# circuit.net
KiCad netlist of a schematic drawn in EAGLE
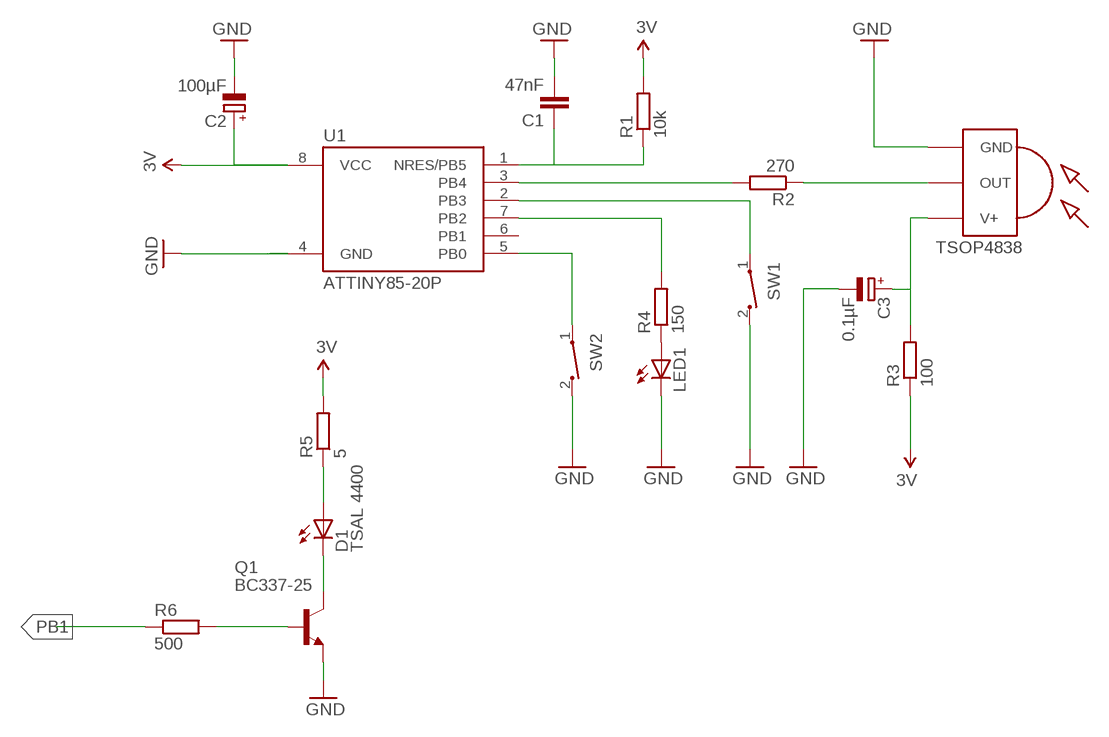
[diagram p0: schematic, sheet 1]

(export (version "E")
  (design (tool "Eeschema 10.0.6"))
  (components
    (comp (ref "C1")
      (value "47nF")
      (footprint "eagle-import:C025-025X050")
      (libsource (lib "eagle-import") (part "C-EU025-025X050"))
    )
    (comp (ref "C2")
      (value "100µF")
      (footprint "eagle-import:085CS_1AR")
      (libsource (lib "eagle-import") (part "CPOL-EU085CS-1AR"))
    )
    (comp (ref "C3")
      (value "0.1µF")
      (footprint "eagle-import:085CS_1AR")
      (libsource (lib "eagle-import") (part "CPOL-EU085CS-1AR"))
    )
    (comp (ref "D1")
      (value "TSAL 4400")
      (footprint "eagle-import:SFH482")
      (libsource (lib "eagle-import") (part "SFH482"))
    )
    (comp (ref "LED1")
      (value "LED5MM")
      (footprint "eagle-import:LED5MM")
      (libsource (lib "eagle-import") (part "LED5MM"))
    )
    (comp (ref "Q1")
      (value "BC337-25")
      (footprint "eagle-import:TO92")
      (libsource (lib "eagle-import") (part "BC337"))
    )
    (comp (ref "R1")
      (value "10k")
      (footprint "eagle-import:0204V")
      (libsource (lib "eagle-import") (part "R-EU_0204/2V"))
    )
    (comp (ref "R2")
      (value "270")
      (footprint "eagle-import:0204V")
      (libsource (lib "eagle-import") (part "R-EU_0204/2V"))
    )
    (comp (ref "R3")
      (value "100")
      (footprint "eagle-import:0204V")
      (libsource (lib "eagle-import") (part "R-EU_0204/2V"))
    )
    (comp (ref "R4")
      (value "150")
      (footprint "eagle-import:0204V")
      (libsource (lib "eagle-import") (part "R-EU_0204/2V"))
    )
    (comp (ref "R5")
      (value "5")
      (footprint "eagle-import:0204V")
      (libsource (lib "eagle-import") (part "R-EU_0204/2V"))
    )
    (comp (ref "R6")
      (value "500")
      (footprint "eagle-import:0204V")
      (libsource (lib "eagle-import") (part "R-EU_0204/2V"))
    )
    (comp (ref "SW1")
      (value "CT10-XXXX-A2")
      (footprint "eagle-import:CT10-XXXX-A2")
      (libsource (lib "eagle-import") (part "CT10-XXXX-A2"))
    )
    (comp (ref "SW2")
      (value "CT10-XXXX-A2")
      (footprint "eagle-import:CT10-XXXX-A2")
      (libsource (lib "eagle-import") (part "CT10-XXXX-A2"))
    )
    (comp (ref "U$1")
      (value "TSOP4838")
      (footprint "eagle-import:TSOP18XX")
      (libsource (lib "eagle-import") (part "TSOP4838"))
    )
    (comp (ref "U1")
      (value "ATTINY85-20P")
      (footprint "eagle-import:PDIP08_300MIL")
      (libsource (lib "eagle-import") (part "ATTINY85P-20"))
    )
  )
  (nets
    (net (code "1") (name "3V") (class "Default")
      (node (ref "C2") (pin "+") (pinfunction "+_+") (pintype "passive"))
      (node (ref "R1") (pin "2") (pinfunction "2_2") (pintype "passive"))
      (node (ref "R3") (pin "1") (pinfunction "1_1") (pintype "passive"))
      (node (ref "R5") (pin "2") (pinfunction "2_2") (pintype "passive"))
      (node (ref "U1") (pin "8") (pinfunction "VCC_8") (pintype "power_in"))
    )
    (net (code "2") (name "GND") (class "Default")
      (node (ref "C1") (pin "2") (pinfunction "2_2") (pintype "passive"))
      (node (ref "C2") (pin "-") (pinfunction "-_-") (pintype "passive"))
      (node (ref "C3") (pin "-") (pinfunction "-_-") (pintype "passive"))
      (node (ref "LED1") (pin "K") (pinfunction "C_K") (pintype "passive"))
      (node (ref "Q1") (pin "1") (pinfunction "E_1") (pintype "passive"))
      (node (ref "SW1") (pin "2") (pinfunction "2_2") (pintype "passive"))
      (node (ref "SW2") (pin "2") (pinfunction "2_2") (pintype "passive"))
      (node (ref "U$1") (pin "GND") (pinfunction "GND_GND") (pintype "bidirectional"))
      (node (ref "U1") (pin "4") (pinfunction "GND_4") (pintype "power_in"))
    )
    (net (code "3") (name "Net-(D1-C)") (class "Default")
      (node (ref "D1") (pin "K") (pinfunction "C_K") (pintype "passive"))
      (node (ref "Q1") (pin "3") (pinfunction "C_3") (pintype "passive"))
    )
    (net (code "4") (name "Net-(D1-PadA)") (class "Default")
      (node (ref "D1") (pin "A") (pinfunction "A_A") (pintype "passive"))
      (node (ref "R5") (pin "1") (pinfunction "1_1") (pintype "passive"))
    )
    (net (code "5") (name "Net-(LED1-PadA)") (class "Default")
      (node (ref "LED1") (pin "A") (pinfunction "A_A") (pintype "passive"))
      (node (ref "R4") (pin "1") (pinfunction "1_1") (pintype "passive"))
    )
    (net (code "6") (name "Net-(Q1-B)") (class "Default")
      (node (ref "Q1") (pin "2") (pinfunction "B_2") (pintype "passive"))
      (node (ref "R6") (pin "2") (pinfunction "2_2") (pintype "passive"))
    )
    (net (code "7") (name "Net-(R2-Pad1)") (class "Default")
      (node (ref "R2") (pin "1") (pinfunction "1_1") (pintype "passive"))
      (node (ref "U$1") (pin "OUT") (pinfunction "OUT_OUT") (pintype "bidirectional"))
    )
    (net (code "8") (name "Net-(U$1-V+)") (class "Default")
      (node (ref "C3") (pin "+") (pinfunction "+_+") (pintype "passive"))
      (node (ref "R3") (pin "2") (pinfunction "2_2") (pintype "passive"))
      (node (ref "U$1") (pin "VCC") (pinfunction "V+_VCC") (pintype "bidirectional"))
    )
    (net (code "9") (name "Net-(U1-NRES{slash}PB5)") (class "Default")
      (node (ref "R1") (pin "1") (pinfunction "1_1") (pintype "passive"))
      (node (ref "U1") (pin "1") (pinfunction "NRES/PB5_1") (pintype "bidirectional"))
    )
    (net (code "10") (name "Net-(U1-PB0)") (class "Default")
      (node (ref "SW2") (pin "1") (pinfunction "1_1") (pintype "passive"))
      (node (ref "U1") (pin "5") (pinfunction "PB0_5") (pintype "bidirectional"))
    )
    (net (code "11") (name "Net-(U1-PB2)") (class "Default")
      (node (ref "R4") (pin "2") (pinfunction "2_2") (pintype "passive"))
      (node (ref "U1") (pin "7") (pinfunction "PB2_7") (pintype "bidirectional"))
    )
    (net (code "12") (name "Net-(U1-PB3)") (class "Default")
      (node (ref "SW1") (pin "1") (pinfunction "1_1") (pintype "passive"))
      (node (ref "U1") (pin "2") (pinfunction "PB3_2") (pintype "bidirectional"))
    )
    (net (code "13") (name "Net-(U1-PB4)") (class "Default")
      (node (ref "R2") (pin "2") (pinfunction "2_2") (pintype "passive"))
      (node (ref "U1") (pin "3") (pinfunction "PB4_3") (pintype "bidirectional"))
    )
    (net (code "14") (name "PB1") (class "Default")
      (node (ref "R6") (pin "1") (pinfunction "1_1") (pintype "passive"))
    )
    (net (code "15") (name "unconnected-(C1-Pad1)") (class "Default")
      (node (ref "C1") (pin "1") (pinfunction "1_1") (pintype "passive"))
    )
    (net (code "16") (name "unconnected-(U1-PB1-Pad6)") (class "Default")
      (node (ref "U1") (pin "6") (pinfunction "PB1_6") (pintype "bidirectional"))
    )
  )
)
